# FT232RL.net
KiCad netlist of a schematic drawn in Altium Designer
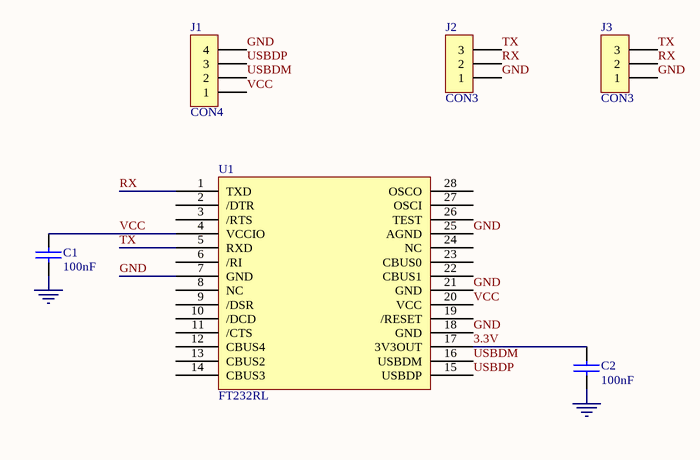
[diagram p0: FT232RL.SCHDOC]

(export (version "E")
  (design (tool "Eeschema 10.0.6"))
  (components
    (comp (ref "C1")
      (value "100nF")
      (footprint "0603")
      (description "Capacitor")
      (libsource (lib "Miscellaneous Devices") (part "CAP"))
    )
    (comp (ref "C2")
      (value "100nF")
      (footprint "0603")
      (description "Capacitor")
      (libsource (lib "Miscellaneous Devices") (part "CAP"))
    )
    (comp (ref "J1")
      (value "CON4")
      (footprint "USB A MALE 2")
      (description "Connector")
      (libsource (lib "Miscellaneous Devices") (part "CON4"))
    )
    (comp (ref "J2")
      (value "CON3")
      (footprint "SIP3")
      (description "Connector")
      (libsource (lib "Miscellaneous Devices") (part "CON3"))
    )
    (comp (ref "J3")
      (value "CON3")
      (footprint "SIP3")
      (description "Connector")
      (libsource (lib "Miscellaneous Devices") (part "CON3"))
    )
    (comp (ref "U1") (value "FT232RL") (footprint "SSOP-28") (libsource (lib "Devices") (part "FT232RL")))
  )
  (nets
    (net (code "1") (name "/3.3V") (class "Default")
      (node (ref "C2") (pin "1") (pinfunction "1_1") (pintype "passive"))
      (node (ref "U1") (pin "17") (pinfunction "3V3OUT_17") (pintype "passive"))
    )
    (net (code "2") (name "/RX") (class "Default")
      (node (ref "J2") (pin "2") (pinfunction "2_2") (pintype "passive"))
      (node (ref "J3") (pin "2") (pinfunction "2_2") (pintype "passive"))
      (node (ref "U1") (pin "1") (pinfunction "TXD_1") (pintype "passive"))
    )
    (net (code "3") (name "/TX") (class "Default")
      (node (ref "J2") (pin "3") (pinfunction "3_3") (pintype "passive"))
      (node (ref "J3") (pin "3") (pinfunction "3_3") (pintype "passive"))
      (node (ref "U1") (pin "5") (pinfunction "RXD_5") (pintype "passive"))
    )
    (net (code "4") (name "/USBDM") (class "Default")
      (node (ref "J1") (pin "2") (pinfunction "2_2") (pintype "passive"))
      (node (ref "U1") (pin "16") (pinfunction "USBDM_16") (pintype "passive"))
    )
    (net (code "5") (name "/USBDP") (class "Default")
      (node (ref "J1") (pin "3") (pinfunction "3_3") (pintype "passive"))
      (node (ref "U1") (pin "15") (pinfunction "USBDP_15") (pintype "passive"))
    )
    (net (code "6") (name "/VCC") (class "Default")
      (node (ref "C1") (pin "1") (pinfunction "1_1") (pintype "passive"))
      (node (ref "J1") (pin "1") (pinfunction "1_1") (pintype "passive"))
      (node (ref "U1") (pin "20") (pinfunction "VCC_20") (pintype "passive"))
      (node (ref "U1") (pin "4") (pinfunction "VCCIO_4") (pintype "passive"))
    )
    (net (code "7") (name "GND") (class "Default")
      (node (ref "C1") (pin "2") (pinfunction "2_2") (pintype "passive"))
      (node (ref "C2") (pin "2") (pinfunction "2_2") (pintype "passive"))
      (node (ref "J1") (pin "4") (pinfunction "4_4") (pintype "passive"))
      (node (ref "J2") (pin "1") (pinfunction "1_1") (pintype "passive"))
      (node (ref "J3") (pin "1") (pinfunction "1_1") (pintype "passive"))
      (node (ref "U1") (pin "18") (pinfunction "GND_18") (pintype "passive"))
      (node (ref "U1") (pin "21") (pinfunction "GND_21") (pintype "passive"))
      (node (ref "U1") (pin "25") (pinfunction "AGND_25") (pintype "passive"))
      (node (ref "U1") (pin "7") (pinfunction "GND_7") (pintype "passive"))
    )
    (net (code "8") (name "unconnected-(U1-CBUS0-Pad23)") (class "Default")
      (node (ref "U1") (pin "23") (pinfunction "CBUS0_23") (pintype "passive"))
    )
    (net (code "9") (name "unconnected-(U1-CBUS1-Pad22)") (class "Default")
      (node (ref "U1") (pin "22") (pinfunction "CBUS1_22") (pintype "passive"))
    )
    (net (code "10") (name "unconnected-(U1-CBUS2-Pad13)") (class "Default")
      (node (ref "U1") (pin "13") (pinfunction "CBUS2_13") (pintype "passive"))
    )
    (net (code "11") (name "unconnected-(U1-CBUS3-Pad14)") (class "Default")
      (node (ref "U1") (pin "14") (pinfunction "CBUS3_14") (pintype "passive"))
    )
    (net (code "12") (name "unconnected-(U1-CBUS4-Pad12)") (class "Default")
      (node (ref "U1") (pin "12") (pinfunction "CBUS4_12") (pintype "passive"))
    )
    (net (code "13") (name "unconnected-(U1-NC-Pad8)") (class "Default")
      (node (ref "U1") (pin "8") (pinfunction "NC_8") (pintype "passive"))
    )
    (net (code "14") (name "unconnected-(U1-NC-Pad24)") (class "Default")
      (node (ref "U1") (pin "24") (pinfunction "NC_24") (pintype "passive"))
    )
    (net (code "15") (name "unconnected-(U1-OSCI-Pad27)") (class "Default")
      (node (ref "U1") (pin "27") (pinfunction "OSCI_27") (pintype "passive"))
    )
    (net (code "16") (name "unconnected-(U1-OSCO-Pad28)") (class "Default")
      (node (ref "U1") (pin "28") (pinfunction "OSCO_28") (pintype "passive"))
    )
    (net (code "17") (name "unconnected-(U1-TEST-Pad26)") (class "Default")
      (node (ref "U1") (pin "26") (pinfunction "TEST_26") (pintype "passive"))
    )
    (net (code "18") (name "unconnected-(U1-{slash}CTS-Pad11)") (class "Default")
      (node (ref "U1") (pin "11") (pinfunction "/CTS_11") (pintype "passive"))
    )
    (net (code "19") (name "unconnected-(U1-{slash}DCD-Pad10)") (class "Default")
      (node (ref "U1") (pin "10") (pinfunction "/DCD_10") (pintype "passive"))
    )
    (net (code "20") (name "unconnected-(U1-{slash}DSR-Pad9)") (class "Default")
      (node (ref "U1") (pin "9") (pinfunction "/DSR_9") (pintype "passive"))
    )
    (net (code "21") (name "unconnected-(U1-{slash}DTR-Pad2)") (class "Default")
      (node (ref "U1") (pin "2") (pinfunction "/DTR_2") (pintype "passive"))
    )
    (net (code "22") (name "unconnected-(U1-{slash}RESET-Pad19)") (class "Default")
      (node (ref "U1") (pin "19") (pinfunction "/RESET_19") (pintype "passive"))
    )
    (net (code "23") (name "unconnected-(U1-{slash}RI-Pad6)") (class "Default")
      (node (ref "U1") (pin "6") (pinfunction "/RI_6") (pintype "passive"))
    )
    (net (code "24") (name "unconnected-(U1-{slash}RTS-Pad3)") (class "Default")
      (node (ref "U1") (pin "3") (pinfunction "/RTS_3") (pintype "passive"))
    )
  )
)
